# sx1509-breakout_mount_remap3.net
KiCad netlist of a schematic drawn in EAGLE
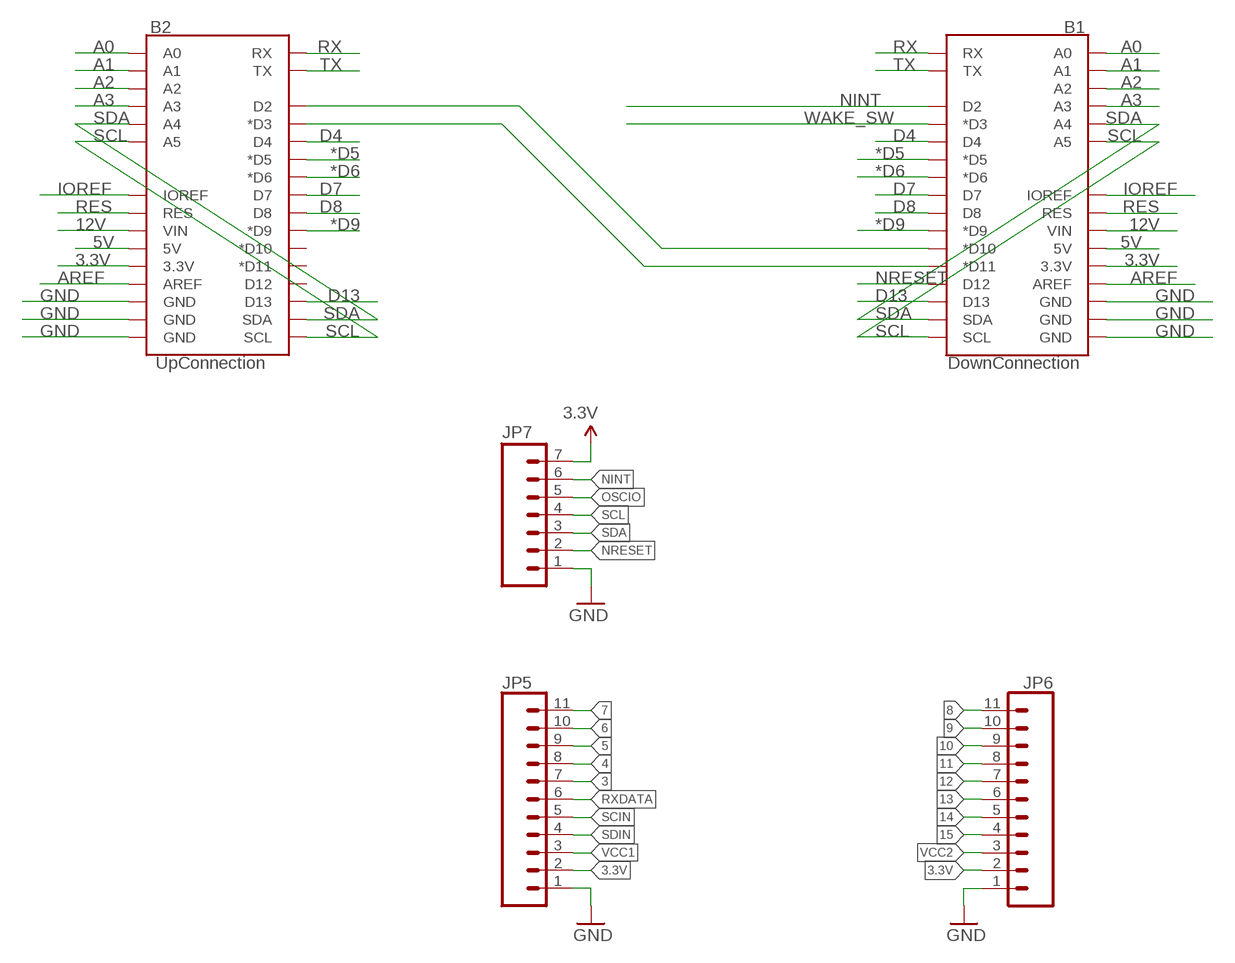
[diagram p0: schematic, sheet 1, part 1 of 2]
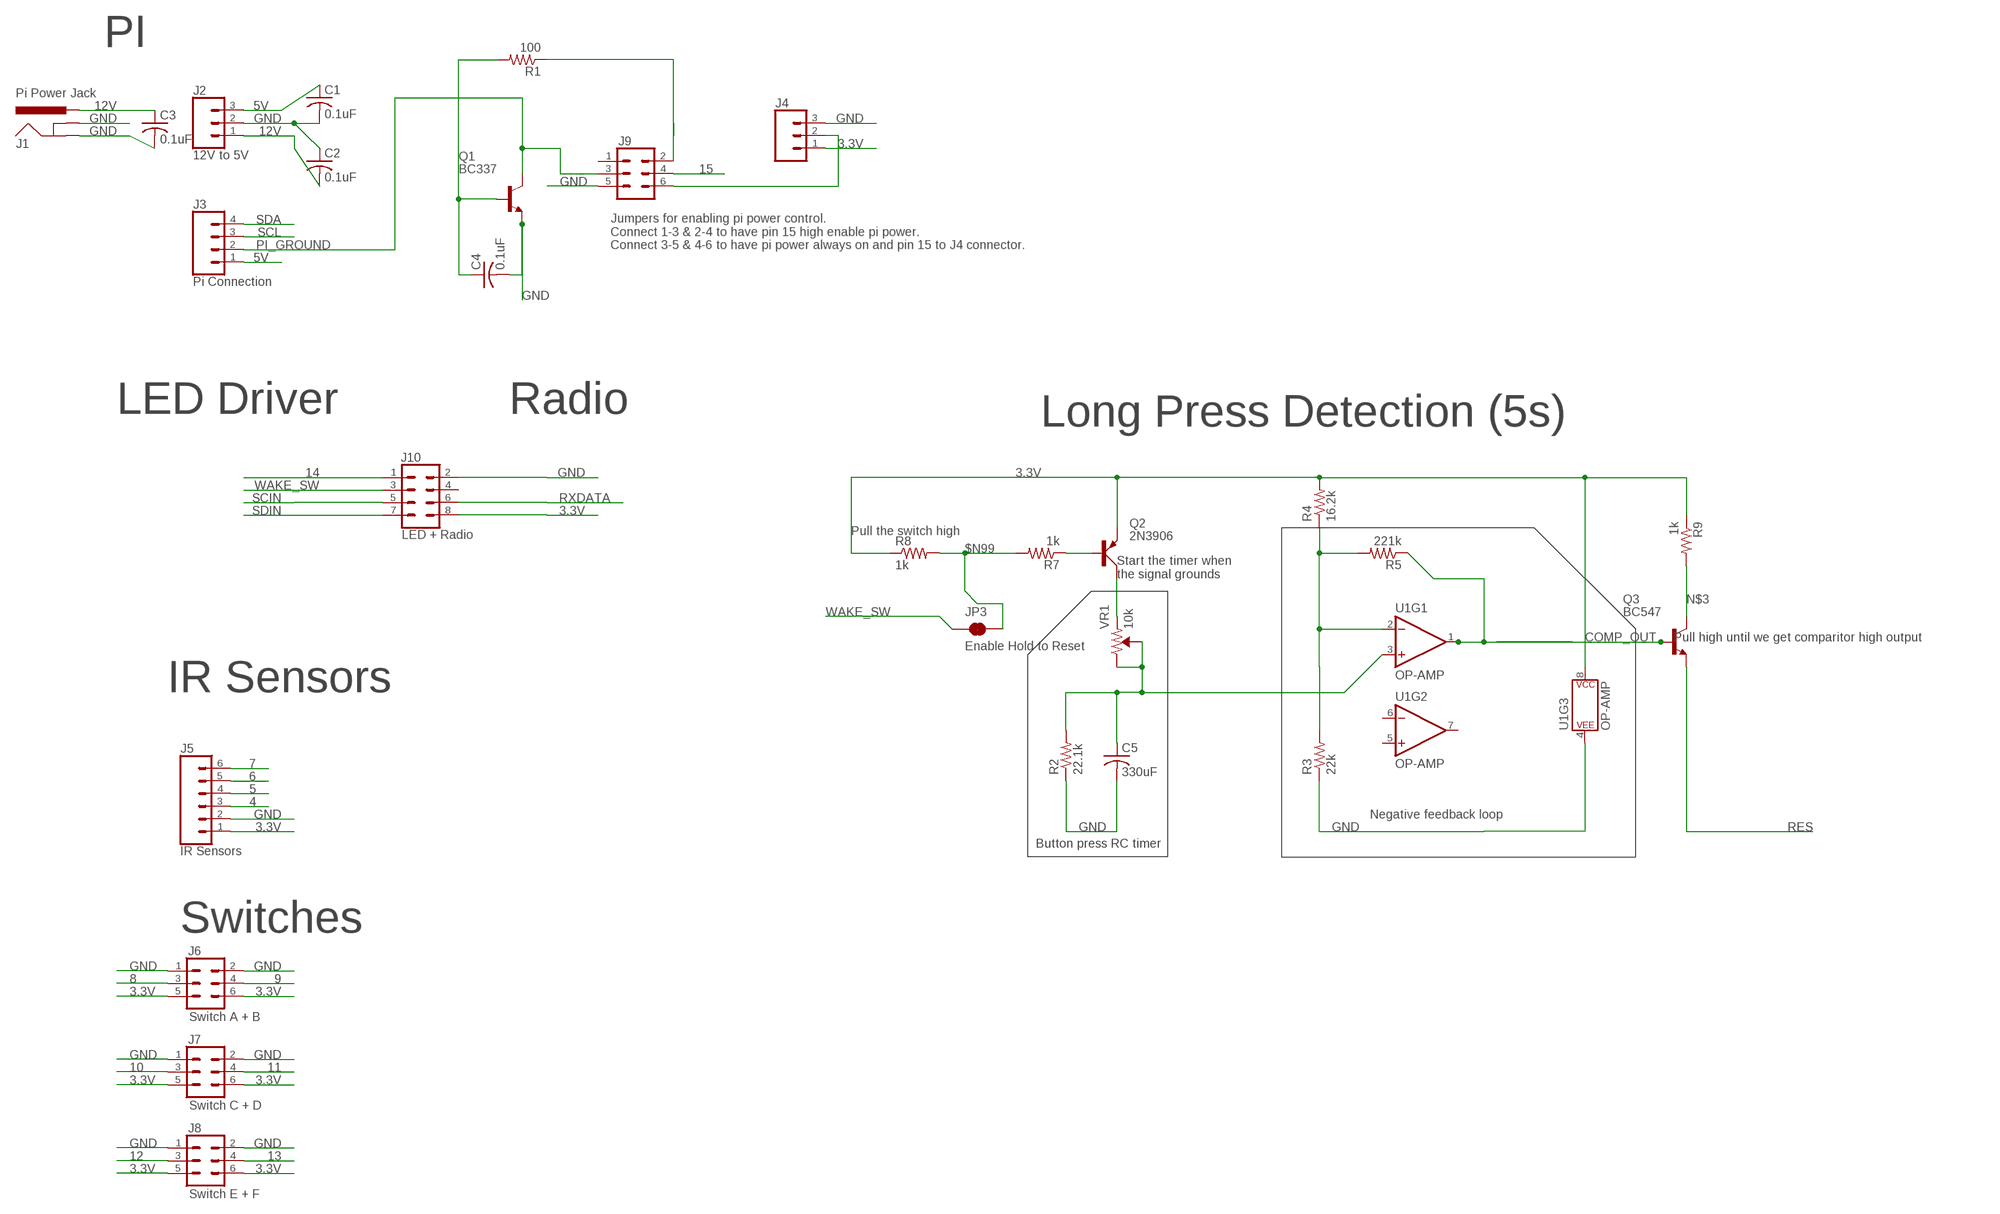
[diagram p1: schematic, sheet 1, part 2 of 2]

(export (version "E")
  (design (tool "Eeschema 10.0.6"))
  (components
    (comp (ref "B1")
      (value "DownConnection")
      (footprint "eagle-import:UNO_R3_SHIELD_NOLABELS")
      (libsource (lib "eagle-import") (part "ARDUINO_UNO_R3_SHIELDNOLABELS"))
    )
    (comp (ref "B2")
      (value "UpConnection")
      (footprint "eagle-import:UNO_R3_SHIELD_NOLABELS")
      (libsource (lib "eagle-import") (part "ARDUINO_UNO_R3_SHIELDNOLABELS"))
    )
    (comp (ref "C1")
      (value "0.1uF")
      (footprint "eagle-import:C0805")
      (libsource (lib "eagle-import") (part "C-USC0805"))
    )
    (comp (ref "C2")
      (value "0.1uF")
      (footprint "eagle-import:C0805")
      (libsource (lib "eagle-import") (part "C-USC0805"))
    )
    (comp (ref "C3")
      (value "0.1uF")
      (footprint "eagle-import:C0805")
      (libsource (lib "eagle-import") (part "C-USC0805"))
    )
    (comp (ref "C4")
      (value "0.1uF")
      (footprint "eagle-import:C0805")
      (libsource (lib "eagle-import") (part "C-USC0805"))
    )
    (comp (ref "C5")
      (value "330uF")
      (footprint "eagle-import:C0805")
      (libsource (lib "eagle-import") (part "C-USC0805"))
    )
    (comp (ref "J1")
      (value "Pi Power Jack")
      (footprint "eagle-import:POWER_JACK_PTH_BREAD")
      (libsource (lib "eagle-import") (part "POWER_JACKPTH_BREAD"))
    )
    (comp (ref "J2")
      (value "12V to 5V")
      (footprint "eagle-import:1X03")
      (libsource (lib "eagle-import") (part "CONN_03"))
    )
    (comp (ref "J3")
      (value "Pi Connection")
      (footprint "eagle-import:1X04")
      (libsource (lib "eagle-import") (part "CONN_04"))
    )
    (comp (ref "J4")
      (value "CONN_03")
      (footprint "eagle-import:1X03")
      (libsource (lib "eagle-import") (part "CONN_03"))
    )
    (comp (ref "J5")
      (value "IR Sensors")
      (footprint "eagle-import:1X06")
      (libsource (lib "eagle-import") (part "CONN_06SILK_FEMALE_PTH"))
    )
    (comp (ref "J6")
      (value "Switch A + B")
      (footprint "eagle-import:2X3")
      (libsource (lib "eagle-import") (part "CONN_03X2FEMALE"))
    )
    (comp (ref "J7")
      (value "Switch C + D")
      (footprint "eagle-import:2X3")
      (libsource (lib "eagle-import") (part "CONN_03X2FEMALE"))
    )
    (comp (ref "J8")
      (value "Switch E + F")
      (footprint "eagle-import:2X3")
      (libsource (lib "eagle-import") (part "CONN_03X2FEMALE"))
    )
    (comp (ref "J9")
      (value "CONN_03X2NO_SILK")
      (footprint "eagle-import:2X3-NS")
      (libsource (lib "eagle-import") (part "CONN_03X2NO_SILK"))
    )
    (comp (ref "J10")
      (value "LED + Radio")
      (footprint "eagle-import:2X4")
      (libsource (lib "eagle-import") (part "CONN_04X2"))
    )
    (comp (ref "JP3")
      (value "Enable Hold to Reset")
      (footprint "eagle-import:SMT-JUMPER_2_NC_TRACE_SILK")
      (libsource (lib "eagle-import") (part "JUMPER-SMT_2_NC_TRACE_SILK"))
    )
    (comp (ref "JP5")
      (value "CONN_11")
      (footprint "eagle-import:1X11")
      (libsource (lib "eagle-import") (part "CONN_11"))
    )
    (comp (ref "JP6")
      (value "CONN_11")
      (footprint "eagle-import:1X11")
      (libsource (lib "eagle-import") (part "CONN_11"))
    )
    (comp (ref "JP7")
      (value "M07")
      (footprint "eagle-import:1X07")
      (libsource (lib "eagle-import") (part "M07"))
    )
    (comp (ref "Q1")
      (value "BC337")
      (footprint "eagle-import:TO92")
      (libsource (lib "eagle-import") (part "BC337"))
    )
    (comp (ref "Q2")
      (value "2N3906")
      (footprint "eagle-import:TO92D")
      (libsource (lib "eagle-import") (part "2N3906"))
    )
    (comp (ref "Q3")
      (value "BC547")
      (footprint "eagle-import:TO92")
      (fields (field (name "NOTE") "Pull high until we get comparitor high output"))
      (libsource (lib "eagle-import") (part "BC547"))
    )
    (comp (ref "R1")
      (value "100")
      (footprint "eagle-import:R0805")
      (libsource (lib "eagle-import") (part "R-US_R0805"))
    )
    (comp (ref "R2")
      (value "22.1k")
      (footprint "eagle-import:R0805")
      (libsource (lib "eagle-import") (part "R-US_R0805"))
    )
    (comp (ref "R3")
      (value "22k")
      (footprint "eagle-import:R0805")
      (libsource (lib "eagle-import") (part "R-US_R0805"))
    )
    (comp (ref "R4")
      (value "16.2k")
      (footprint "eagle-import:R0805")
      (libsource (lib "eagle-import") (part "R-US_R0805"))
    )
    (comp (ref "R5")
      (value "221k")
      (footprint "eagle-import:R0805")
      (libsource (lib "eagle-import") (part "R-US_R0805"))
    )
    (comp (ref "R7")
      (value "1k")
      (footprint "eagle-import:R0805")
      (libsource (lib "eagle-import") (part "R-US_R0805"))
    )
    (comp (ref "R8")
      (value "1k")
      (footprint "eagle-import:R0805")
      (fields (field (name "NOTE") "Pull the switch high"))
      (libsource (lib "eagle-import") (part "R-US_R0805"))
    )
    (comp (ref "R9")
      (value "1k")
      (footprint "eagle-import:R0805")
      (libsource (lib "eagle-import") (part "R-US_R0805"))
    )
    (comp (ref "U1")
      (value "OP-AMP")
      (footprint "eagle-import:SO08")
      (libsource (lib "eagle-import") (part "OPAMP-DUALU"))
    )
    (comp (ref "VR1")
      (value "10k")
      (footprint "eagle-import:TRIMPOT-PTH-3386U")
      (libsource (lib "eagle-import") (part "TRIMPOT-PTH-10MM-KNOB-1/2W-10%"))
    )
  )
  (nets
    (net (code "1") (name "/$N99") (class "Default")
      (node (ref "JP3") (pin "2") (pinfunction "2_2") (pintype "passive"))
      (node (ref "R7") (pin "2") (pinfunction "2_2") (pintype "passive"))
      (node (ref "R8") (pin "2") (pinfunction "2_2") (pintype "passive"))
    )
    (net (code "2") (name "/*D5") (class "Default")
      (node (ref "B1") (pin "D5") (pinfunction "*D5_D5") (pintype "bidirectional"))
      (node (ref "B2") (pin "D5") (pinfunction "*D5_D5") (pintype "bidirectional"))
    )
    (net (code "3") (name "/*D6") (class "Default")
      (node (ref "B1") (pin "D6") (pinfunction "*D6_D6") (pintype "bidirectional"))
      (node (ref "B2") (pin "D6") (pinfunction "*D6_D6") (pintype "bidirectional"))
    )
    (net (code "4") (name "/*D9") (class "Default")
      (node (ref "B1") (pin "D9") (pinfunction "*D9_D9") (pintype "bidirectional"))
      (node (ref "B2") (pin "D9") (pinfunction "*D9_D9") (pintype "bidirectional"))
    )
    (net (code "5") (name "/5V") (class "Default")
      (node (ref "B1") (pin "5V") (pinfunction "5V_5V") (pintype "bidirectional"))
      (node (ref "B2") (pin "5V") (pinfunction "5V_5V") (pintype "bidirectional"))
      (node (ref "C1") (pin "1") (pinfunction "1_1") (pintype "passive"))
      (node (ref "J2") (pin "3") (pinfunction "3_3") (pintype "passive"))
      (node (ref "J3") (pin "1") (pinfunction "1_1") (pintype "passive"))
    )
    (net (code "6") (name "/12V") (class "Default")
      (node (ref "B1") (pin "VIN") (pinfunction "VIN_VIN") (pintype "bidirectional"))
      (node (ref "B2") (pin "VIN") (pinfunction "VIN_VIN") (pintype "bidirectional"))
      (node (ref "C2") (pin "2") (pinfunction "2_2") (pintype "passive"))
      (node (ref "C3") (pin "1") (pinfunction "1_1") (pintype "passive"))
      (node (ref "J1") (pin "PWR") (pinfunction "PWR_PWR") (pintype "bidirectional"))
      (node (ref "J2") (pin "1") (pinfunction "1_1") (pintype "passive"))
    )
    (net (code "7") (name "/A0") (class "Default")
      (node (ref "B1") (pin "A0") (pinfunction "A0_A0") (pintype "bidirectional"))
      (node (ref "B2") (pin "A0") (pinfunction "A0_A0") (pintype "bidirectional"))
    )
    (net (code "8") (name "/A1") (class "Default")
      (node (ref "B1") (pin "A1") (pinfunction "A1_A1") (pintype "bidirectional"))
      (node (ref "B2") (pin "A1") (pinfunction "A1_A1") (pintype "bidirectional"))
    )
    (net (code "9") (name "/A2") (class "Default")
      (node (ref "B1") (pin "A2") (pinfunction "A2_A2") (pintype "bidirectional"))
      (node (ref "B2") (pin "A2") (pinfunction "A2_A2") (pintype "bidirectional"))
    )
    (net (code "10") (name "/A3") (class "Default")
      (node (ref "B1") (pin "A3") (pinfunction "A3_A3") (pintype "bidirectional"))
      (node (ref "B2") (pin "A3") (pinfunction "A3_A3") (pintype "bidirectional"))
    )
    (net (code "11") (name "/AREF") (class "Default")
      (node (ref "B1") (pin "AREF") (pinfunction "AREF_AREF") (pintype "bidirectional"))
      (node (ref "B2") (pin "AREF") (pinfunction "AREF_AREF") (pintype "bidirectional"))
    )
    (net (code "12") (name "/COMP_OUT") (class "Default")
      (node (ref "Q3") (pin "2") (pinfunction "B_2") (pintype "passive"))
      (node (ref "R5") (pin "1") (pinfunction "1_1") (pintype "passive"))
      (node (ref "U1") (pin "1") (pinfunction "OUT_1") (pintype "output"))
    )
    (net (code "13") (name "/D4") (class "Default")
      (node (ref "B1") (pin "D4") (pinfunction "D4_D4") (pintype "bidirectional"))
      (node (ref "B2") (pin "D4") (pinfunction "D4_D4") (pintype "bidirectional"))
    )
    (net (code "14") (name "/D7") (class "Default")
      (node (ref "B1") (pin "D7") (pinfunction "D7_D7") (pintype "bidirectional"))
      (node (ref "B2") (pin "D7") (pinfunction "D7_D7") (pintype "bidirectional"))
    )
    (net (code "15") (name "/D8") (class "Default")
      (node (ref "B1") (pin "D8") (pinfunction "D8_D8") (pintype "bidirectional"))
      (node (ref "B2") (pin "D8") (pinfunction "D8_D8") (pintype "bidirectional"))
    )
    (net (code "16") (name "/D13") (class "Default")
      (node (ref "B1") (pin "D13") (pinfunction "D13_D13") (pintype "bidirectional"))
      (node (ref "B2") (pin "D13") (pinfunction "D13_D13") (pintype "bidirectional"))
    )
    (net (code "17") (name "/IOREF") (class "Default")
      (node (ref "B1") (pin "IOREF") (pinfunction "IOREF_IOREF") (pintype "bidirectional"))
      (node (ref "B2") (pin "IOREF") (pinfunction "IOREF_IOREF") (pintype "bidirectional"))
    )
    (net (code "18") (name "/N$3") (class "Default")
      (node (ref "Q3") (pin "3") (pinfunction "C_3") (pintype "passive"))
      (node (ref "R9") (pin "2") (pinfunction "2_2") (pintype "passive"))
    )
    (net (code "19") (name "/PI_GROUND") (class "Default")
      (node (ref "J3") (pin "2") (pinfunction "2_2") (pintype "passive"))
      (node (ref "J9") (pin "3") (pinfunction "3_3") (pintype "bidirectional"))
      (node (ref "Q1") (pin "3") (pinfunction "C_3") (pintype "passive"))
    )
    (net (code "20") (name "/RES") (class "Default")
      (node (ref "B1") (pin "RES") (pinfunction "RES_RES") (pintype "bidirectional"))
      (node (ref "B2") (pin "RES") (pinfunction "RES_RES") (pintype "bidirectional"))
      (node (ref "Q3") (pin "1") (pinfunction "E_1") (pintype "passive"))
    )
    (net (code "21") (name "/RX") (class "Default")
      (node (ref "B1") (pin "RX") (pinfunction "RX_RX") (pintype "bidirectional"))
      (node (ref "B2") (pin "RX") (pinfunction "RX_RX") (pintype "bidirectional"))
    )
    (net (code "22") (name "/TX") (class "Default")
      (node (ref "B1") (pin "TX") (pinfunction "TX_TX") (pintype "bidirectional"))
      (node (ref "B2") (pin "TX") (pinfunction "TX_TX") (pintype "bidirectional"))
    )
    (net (code "23") (name "/WAKE_SW") (class "Default")
      (node (ref "B1") (pin "D3") (pinfunction "*D3_D3") (pintype "bidirectional"))
      (node (ref "J10") (pin "3") (pinfunction "3_3") (pintype "passive"))
      (node (ref "JP3") (pin "1") (pinfunction "1_1") (pintype "passive"))
    )
    (net (code "24") (name "3") (class "Default")
      (node (ref "JP5") (pin "7") (pinfunction "7_7") (pintype "passive"))
    )
    (net (code "25") (name "3.3V") (class "Default")
      (node (ref "B1") (pin "3.3V") (pinfunction "3.3V_3.3V") (pintype "bidirectional"))
      (node (ref "B2") (pin "3.3V") (pinfunction "3.3V_3.3V") (pintype "bidirectional"))
      (node (ref "J10") (pin "8") (pinfunction "8_8") (pintype "passive"))
      (node (ref "J4") (pin "1") (pinfunction "1_1") (pintype "passive"))
      (node (ref "J5") (pin "1") (pinfunction "1_1") (pintype "passive"))
      (node (ref "J6") (pin "5") (pinfunction "5_5") (pintype "bidirectional"))
      (node (ref "J6") (pin "6") (pinfunction "6_6") (pintype "bidirectional"))
      (node (ref "J7") (pin "5") (pinfunction "5_5") (pintype "bidirectional"))
      (node (ref "J7") (pin "6") (pinfunction "6_6") (pintype "bidirectional"))
      (node (ref "J8") (pin "5") (pinfunction "5_5") (pintype "bidirectional"))
      (node (ref "J8") (pin "6") (pinfunction "6_6") (pintype "bidirectional"))
      (node (ref "JP5") (pin "2") (pinfunction "2_2") (pintype "passive"))
      (node (ref "JP6") (pin "2") (pinfunction "2_2") (pintype "passive"))
      (node (ref "JP7") (pin "7") (pinfunction "7_7") (pintype "passive"))
      (node (ref "Q2") (pin "E") (pinfunction "E_E") (pintype "passive"))
      (node (ref "R4") (pin "2") (pinfunction "2_2") (pintype "passive"))
      (node (ref "R8") (pin "1") (pinfunction "1_1") (pintype "passive"))
      (node (ref "R9") (pin "1") (pinfunction "1_1") (pintype "passive"))
      (node (ref "U1") (pin "8") (pinfunction "P$V+_8") (pintype "bidirectional"))
    )
    (net (code "26") (name "4") (class "Default")
      (node (ref "J5") (pin "3") (pinfunction "3_3") (pintype "passive"))
      (node (ref "JP5") (pin "8") (pinfunction "8_8") (pintype "passive"))
    )
    (net (code "27") (name "5") (class "Default")
      (node (ref "J5") (pin "4") (pinfunction "4_4") (pintype "passive"))
      (node (ref "JP5") (pin "9") (pinfunction "9_9") (pintype "passive"))
    )
    (net (code "28") (name "6") (class "Default")
      (node (ref "J5") (pin "5") (pinfunction "5_5") (pintype "passive"))
      (node (ref "JP5") (pin "10") (pinfunction "10_10") (pintype "passive"))
    )
    (net (code "29") (name "7") (class "Default")
      (node (ref "J5") (pin "6") (pinfunction "6_6") (pintype "passive"))
      (node (ref "JP5") (pin "11") (pinfunction "11_11") (pintype "passive"))
    )
    (net (code "30") (name "8") (class "Default")
      (node (ref "J6") (pin "3") (pinfunction "3_3") (pintype "bidirectional"))
      (node (ref "JP6") (pin "11") (pinfunction "11_11") (pintype "passive"))
    )
    (net (code "31") (name "9") (class "Default")
      (node (ref "J6") (pin "4") (pinfunction "4_4") (pintype "bidirectional"))
      (node (ref "JP6") (pin "10") (pinfunction "10_10") (pintype "passive"))
    )
    (net (code "32") (name "10") (class "Default")
      (node (ref "J7") (pin "3") (pinfunction "3_3") (pintype "bidirectional"))
      (node (ref "JP6") (pin "9") (pinfunction "9_9") (pintype "passive"))
    )
    (net (code "33") (name "11") (class "Default")
      (node (ref "J7") (pin "4") (pinfunction "4_4") (pintype "bidirectional"))
      (node (ref "JP6") (pin "8") (pinfunction "8_8") (pintype "passive"))
    )
    (net (code "34") (name "12") (class "Default")
      (node (ref "J8") (pin "3") (pinfunction "3_3") (pintype "bidirectional"))
      (node (ref "JP6") (pin "7") (pinfunction "7_7") (pintype "passive"))
    )
    (net (code "35") (name "13") (class "Default")
      (node (ref "J8") (pin "4") (pinfunction "4_4") (pintype "bidirectional"))
      (node (ref "JP6") (pin "6") (pinfunction "6_6") (pintype "passive"))
    )
    (net (code "36") (name "14") (class "Default")
      (node (ref "J10") (pin "1") (pinfunction "1_1") (pintype "passive"))
      (node (ref "JP6") (pin "5") (pinfunction "5_5") (pintype "passive"))
    )
    (net (code "37") (name "15") (class "Default")
      (node (ref "J9") (pin "4") (pinfunction "4_4") (pintype "bidirectional"))
      (node (ref "JP6") (pin "4") (pinfunction "4_4") (pintype "passive"))
    )
    (net (code "38") (name "GND") (class "Default")
      (node (ref "B1") (pin "GND@0") (pinfunction "GND_GND@0") (pintype "bidirectional"))
      (node (ref "B1") (pin "GND@1") (pinfunction "GND_GND@1") (pintype "bidirectional"))
      (node (ref "B1") (pin "GND@2") (pinfunction "GND_GND@2") (pintype "bidirectional"))
      (node (ref "B2") (pin "GND@0") (pinfunction "GND_GND@0") (pintype "bidirectional"))
      (node (ref "B2") (pin "GND@1") (pinfunction "GND_GND@1") (pintype "bidirectional"))
      (node (ref "B2") (pin "GND@2") (pinfunction "GND_GND@2") (pintype "bidirectional"))
      (node (ref "C1") (pin "2") (pinfunction "2_2") (pintype "passive"))
      (node (ref "C2") (pin "1") (pinfunction "1_1") (pintype "passive"))
      (node (ref "C3") (pin "2") (pinfunction "2_2") (pintype "passive"))
      (node (ref "C4") (pin "2") (pinfunction "2_2") (pintype "passive"))
      (node (ref "C5") (pin "2") (pinfunction "2_2") (pintype "passive"))
      (node (ref "J1") (pin "GND") (pinfunction "GND_GND") (pintype "bidirectional"))
      (node (ref "J1") (pin "GNDBREAK") (pinfunction "GNDBREAK_GNDBREAK") (pintype "bidirectional"))
      (node (ref "J10") (pin "2") (pinfunction "2_2") (pintype "passive"))
      (node (ref "J2") (pin "2") (pinfunction "2_2") (pintype "passive"))
      (node (ref "J4") (pin "3") (pinfunction "3_3") (pintype "passive"))
      (node (ref "J5") (pin "2") (pinfunction "2_2") (pintype "passive"))
      (node (ref "J6") (pin "1") (pinfunction "1_1") (pintype "bidirectional"))
      (node (ref "J6") (pin "2") (pinfunction "2_2") (pintype "bidirectional"))
      (node (ref "J7") (pin "1") (pinfunction "1_1") (pintype "bidirectional"))
      (node (ref "J7") (pin "2") (pinfunction "2_2") (pintype "bidirectional"))
      (node (ref "J8") (pin "1") (pinfunction "1_1") (pintype "bidirectional"))
      (node (ref "J8") (pin "2") (pinfunction "2_2") (pintype "bidirectional"))
      (node (ref "J9") (pin "5") (pinfunction "5_5") (pintype "bidirectional"))
      (node (ref "JP5") (pin "1") (pinfunction "1_1") (pintype "passive"))
      (node (ref "JP6") (pin "1") (pinfunction "1_1") (pintype "passive"))
      (node (ref "JP7") (pin "1") (pinfunction "1_1") (pintype "passive"))
      (node (ref "Q1") (pin "1") (pinfunction "E_1") (pintype "passive"))
      (node (ref "R2") (pin "1") (pinfunction "1_1") (pintype "passive"))
      (node (ref "R3") (pin "1") (pinfunction "1_1") (pintype "passive"))
      (node (ref "U1") (pin "4") (pinfunction "P$V-_4") (pintype "bidirectional"))
    )
    (net (code "39") (name "NINT") (class "Default")
      (node (ref "B1") (pin "D2") (pinfunction "D2_D2") (pintype "bidirectional"))
      (node (ref "JP7") (pin "6") (pinfunction "6_6") (pintype "passive"))
    )
    (net (code "40") (name "NRESET") (class "Default")
      (node (ref "B1") (pin "D12") (pinfunction "D12_D12") (pintype "bidirectional"))
      (node (ref "JP7") (pin "2") (pinfunction "2_2") (pintype "passive"))
    )
    (net (code "41") (name "Net-(B1-*D10)") (class "Default")
      (node (ref "B1") (pin "D10") (pinfunction "*D10_D10") (pintype "bidirectional"))
      (node (ref "B2") (pin "D2") (pinfunction "D2_D2") (pintype "bidirectional"))
    )
    (net (code "42") (name "Net-(B1-*D11)") (class "Default")
      (node (ref "B1") (pin "D11") (pinfunction "*D11_D11") (pintype "bidirectional"))
      (node (ref "B2") (pin "D3") (pinfunction "*D3_D3") (pintype "bidirectional"))
    )
    (net (code "43") (name "Net-(J4-Pad2)") (class "Default")
      (node (ref "J4") (pin "2") (pinfunction "2_2") (pintype "passive"))
      (node (ref "J9") (pin "6") (pinfunction "6_6") (pintype "bidirectional"))
    )
    (net (code "44") (name "Net-(J9-Pad2)") (class "Default")
      (node (ref "J9") (pin "2") (pinfunction "2_2") (pintype "bidirectional"))
      (node (ref "R1") (pin "1") (pinfunction "1_1") (pintype "passive"))
    )
    (net (code "45") (name "Net-(Q1-B)") (class "Default")
      (node (ref "C4") (pin "1") (pinfunction "1_1") (pintype "passive"))
      (node (ref "Q1") (pin "2") (pinfunction "B_2") (pintype "passive"))
      (node (ref "R1") (pin "2") (pinfunction "2_2") (pintype "passive"))
    )
    (net (code "46") (name "Net-(Q2-PadB)") (class "Default")
      (node (ref "Q2") (pin "B") (pinfunction "B_B") (pintype "passive"))
      (node (ref "R7") (pin "1") (pinfunction "1_1") (pintype "passive"))
    )
    (net (code "47") (name "Net-(U1A-+IN)") (class "Default")
      (node (ref "C5") (pin "1") (pinfunction "1_1") (pintype "passive"))
      (node (ref "R2") (pin "2") (pinfunction "2_2") (pintype "passive"))
      (node (ref "U1") (pin "3") (pinfunction "+IN_3") (pintype "input"))
      (node (ref "VR1") (pin "2") (pinfunction "WIPER_2") (pintype "passive"))
      (node (ref "VR1") (pin "3") (pinfunction "CW_3") (pintype "passive"))
    )
    (net (code "48") (name "Net-(U1A--IN)") (class "Default")
      (node (ref "R3") (pin "2") (pinfunction "2_2") (pintype "passive"))
      (node (ref "R4") (pin "1") (pinfunction "1_1") (pintype "passive"))
      (node (ref "R5") (pin "2") (pinfunction "2_2") (pintype "passive"))
      (node (ref "U1") (pin "2") (pinfunction "-IN_2") (pintype "input"))
    )
    (net (code "49") (name "Net-(VR1-CCW)") (class "Default")
      (node (ref "Q2") (pin "C") (pinfunction "C_C") (pintype "passive"))
      (node (ref "VR1") (pin "1") (pinfunction "CCW_1") (pintype "passive"))
    )
    (net (code "50") (name "OSCIO") (class "Default")
      (node (ref "JP7") (pin "5") (pinfunction "5_5") (pintype "passive"))
    )
    (net (code "51") (name "RXDATA") (class "Default")
      (node (ref "J10") (pin "6") (pinfunction "6_6") (pintype "passive"))
      (node (ref "JP5") (pin "6") (pinfunction "6_6") (pintype "passive"))
    )
    (net (code "52") (name "SCIN") (class "Default")
      (node (ref "J10") (pin "5") (pinfunction "5_5") (pintype "passive"))
      (node (ref "JP5") (pin "5") (pinfunction "5_5") (pintype "passive"))
    )
    (net (code "53") (name "SCL") (class "Default")
      (node (ref "B1") (pin "A5") (pinfunction "A5_A5") (pintype "bidirectional"))
      (node (ref "B1") (pin "SCL") (pinfunction "SCL_SCL") (pintype "bidirectional"))
      (node (ref "B2") (pin "A5") (pinfunction "A5_A5") (pintype "bidirectional"))
      (node (ref "B2") (pin "SCL") (pinfunction "SCL_SCL") (pintype "bidirectional"))
      (node (ref "J3") (pin "3") (pinfunction "3_3") (pintype "passive"))
      (node (ref "JP7") (pin "4") (pinfunction "4_4") (pintype "passive"))
    )
    (net (code "54") (name "SDA") (class "Default")
      (node (ref "B1") (pin "A4") (pinfunction "A4_A4") (pintype "bidirectional"))
      (node (ref "B1") (pin "SDA") (pinfunction "SDA_SDA") (pintype "bidirectional"))
      (node (ref "B2") (pin "A4") (pinfunction "A4_A4") (pintype "bidirectional"))
      (node (ref "B2") (pin "SDA") (pinfunction "SDA_SDA") (pintype "bidirectional"))
      (node (ref "J3") (pin "4") (pinfunction "4_4") (pintype "passive"))
      (node (ref "JP7") (pin "3") (pinfunction "3_3") (pintype "passive"))
    )
    (net (code "55") (name "SDIN") (class "Default")
      (node (ref "J10") (pin "7") (pinfunction "7_7") (pintype "passive"))
      (node (ref "JP5") (pin "4") (pinfunction "4_4") (pintype "passive"))
    )
    (net (code "56") (name "VCC1") (class "Default")
      (node (ref "JP5") (pin "3") (pinfunction "3_3") (pintype "passive"))
    )
    (net (code "57") (name "VCC2") (class "Default")
      (node (ref "JP6") (pin "3") (pinfunction "3_3") (pintype "passive"))
    )
    (net (code "58") (name "unconnected-(B2-*D10-PadD10)") (class "Default")
      (node (ref "B2") (pin "D10") (pinfunction "*D10_D10") (pintype "bidirectional"))
    )
    (net (code "59") (name "unconnected-(B2-*D11-PadD11)") (class "Default")
      (node (ref "B2") (pin "D11") (pinfunction "*D11_D11") (pintype "bidirectional"))
    )
    (net (code "60") (name "unconnected-(B2-PadD12)") (class "Default")
      (node (ref "B2") (pin "D12") (pinfunction "D12_D12") (pintype "bidirectional"))
    )
    (net (code "61") (name "unconnected-(J9-Pad1)") (class "Default")
      (node (ref "J9") (pin "1") (pinfunction "1_1") (pintype "bidirectional"))
    )
    (net (code "62") (name "unconnected-(J10-Pad4)") (class "Default")
      (node (ref "J10") (pin "4") (pinfunction "4_4") (pintype "passive"))
    )
    (net (code "63") (name "unconnected-(U1B-+IN-Pad5)") (class "Default")
      (node (ref "U1") (pin "5") (pinfunction "+IN_5") (pintype "input"))
    )
    (net (code "64") (name "unconnected-(U1B--IN-Pad6)") (class "Default")
      (node (ref "U1") (pin "6") (pinfunction "-IN_6") (pintype "input"))
    )
    (net (code "65") (name "unconnected-(U1B-OUT-Pad7)") (class "Default")
      (node (ref "U1") (pin "7") (pinfunction "OUT_7") (pintype "output"))
    )
  )
)
